# ucl.net
KiCad netlist of a schematic drawn in EAGLE
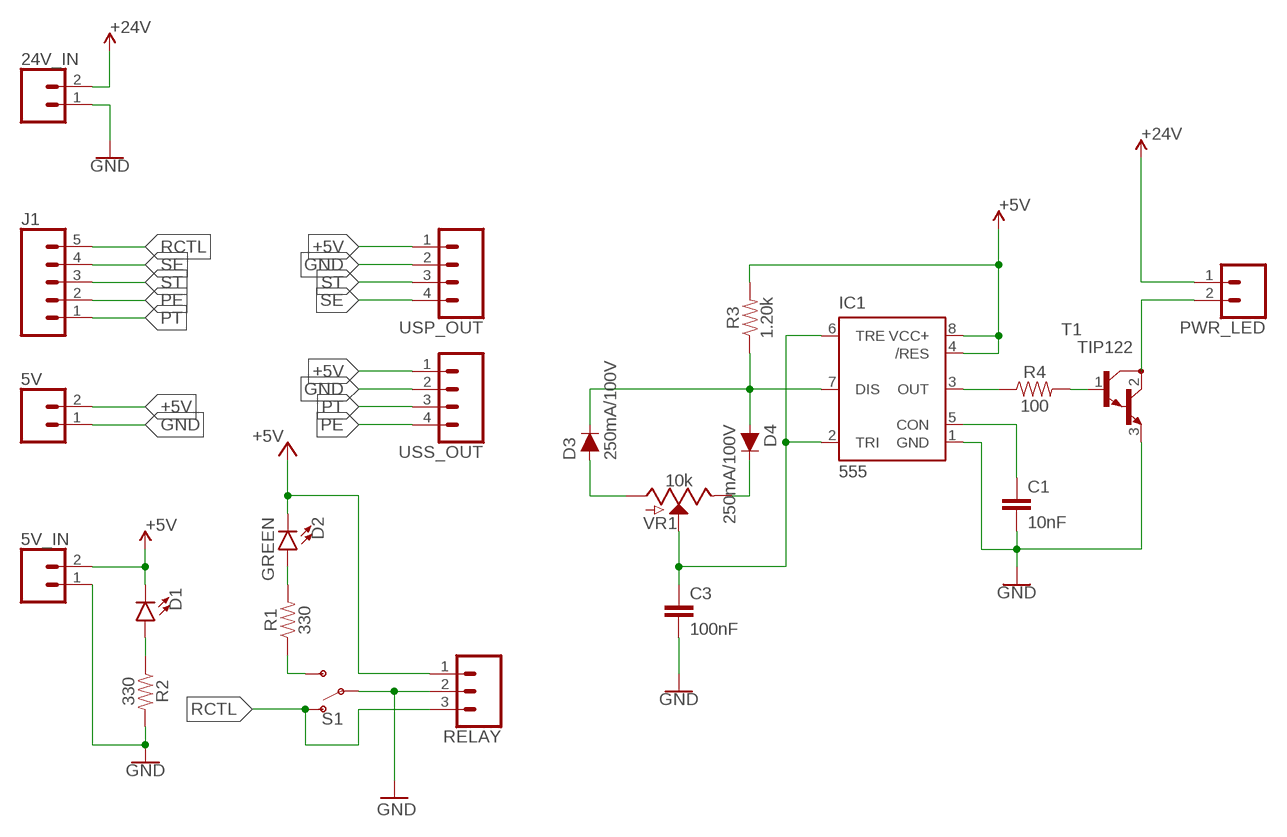
[diagram p0: schematic, sheet 1]

(export (version "E")
  (design (tool "Eeschema 10.0.6"))
  (components
    (comp (ref "5V")
      (value "CONN_02POLAR")
      (footprint "eagle-import:MOLEX-1X2")
      (libsource (lib "eagle-import") (part "CONN_02POLAR"))
    )
    (comp (ref "5V_IN")
      (value "CONN_02POLAR_LOCK")
      (footprint "eagle-import:MOLEX-1X2_LOCK")
      (libsource (lib "eagle-import") (part "CONN_02POLAR_LOCK"))
    )
    (comp (ref "24V_IN")
      (value "CONN_02POLAR_LOCK")
      (footprint "eagle-import:MOLEX-1X2_LOCK")
      (libsource (lib "eagle-import") (part "CONN_02POLAR_LOCK"))
    )
    (comp (ref "C1")
      (value "10nF")
      (footprint "eagle-import:0402-TIGHT")
      (libsource (lib "eagle-import") (part "10NF-0402T-25V-10%"))
    )
    (comp (ref "C3")
      (value "100nF")
      (footprint "eagle-import:0402-TIGHT")
      (libsource (lib "eagle-import") (part "47NF-0402_TIGHT-25V-10%-X7R"))
    )
    (comp (ref "D1")
      (value "LED1206")
      (footprint "eagle-import:LED-1206")
      (libsource (lib "eagle-import") (part "LED1206"))
    )
    (comp (ref "D2")
      (value "GREEN")
      (footprint "eagle-import:LED-1206")
      (libsource (lib "eagle-import") (part "LED-GREEN1206"))
    )
    (comp (ref "D3")
      (value "250mA/100V")
      (footprint "eagle-import:SOD-323")
      (libsource (lib "eagle-import") (part "DIODE-BAS16J"))
    )
    (comp (ref "D4")
      (value "250mA/100V")
      (footprint "eagle-import:SOD-323")
      (libsource (lib "eagle-import") (part "DIODE-BAS16J"))
    )
    (comp (ref "IC1")
      (value "555")
      (footprint "eagle-import:SO08")
      (libsource (lib "eagle-import") (part "555D"))
    )
    (comp (ref "J1")
      (value "CONN_05")
      (footprint "eagle-import:1X05")
      (libsource (lib "eagle-import") (part "CONN_05"))
    )
    (comp (ref "PWR_LED")
      (value "CONN_02POLAR_LOCK")
      (footprint "eagle-import:MOLEX-1X2_LOCK")
      (libsource (lib "eagle-import") (part "CONN_02POLAR_LOCK"))
    )
    (comp (ref "R1")
      (value "330")
      (footprint "eagle-import:0603")
      (libsource (lib "eagle-import") (part "330OHM-0603-1/10W-1%"))
    )
    (comp (ref "R2")
      (value "330")
      (footprint "eagle-import:0603")
      (libsource (lib "eagle-import") (part "330OHM-0603-1/10W-1%"))
    )
    (comp (ref "R3")
      (value "1.20k")
      (footprint "eagle-import:0603")
      (libsource (lib "eagle-import") (part "1.20KOHM-0603-1/10W-1%"))
    )
    (comp (ref "R4")
      (value "100")
      (footprint "eagle-import:0603")
      (libsource (lib "eagle-import") (part "100OHM-0603-1/4W-5%"))
    )
    (comp (ref "RELAY")
      (value "CONN_03POLAR_LOCK")
      (footprint "eagle-import:MOLEX-1X3_LOCK")
      (libsource (lib "eagle-import") (part "CONN_03POLAR_LOCK"))
    )
    (comp (ref "S1")
      (value "SWITCH-SPDT-PTH-11.6X4.0MM-KIT")
      (footprint "eagle-import:SWITCH_SPDT_PTH_11.6X4.0MM_KIT")
      (libsource (lib "eagle-import") (part "SWITCH-SPDT-PTH-11.6X4.0MM-KIT"))
    )
    (comp (ref "T1")
      (value "TIP122")
      (footprint "eagle-import:TO220")
      (libsource (lib "eagle-import") (part "TIP122"))
    )
    (comp (ref "USP_OUT")
      (value "CONN_04POLAR_LOCK")
      (footprint "eagle-import:MOLEX-1X4_LOCK")
      (libsource (lib "eagle-import") (part "CONN_04POLAR_LOCK"))
    )
    (comp (ref "USS_OUT")
      (value "CONN_04POLAR_LOCK")
      (footprint "eagle-import:MOLEX-1X4_LOCK")
      (libsource (lib "eagle-import") (part "CONN_04POLAR_LOCK"))
    )
    (comp (ref "VR1")
      (value "10k")
      (footprint "eagle-import:POT-PTH-ALPS")
      (libsource (lib "eagle-import") (part "POTENTIOMETER-PTH-9MM-1/20W-20%"))
    )
  )
  (nets
    (net (code "1") (name "+5V") (class "Default")
      (node (ref "5V") (pin "2") (pinfunction "2_2") (pintype "passive"))
      (node (ref "5V_IN") (pin "2") (pinfunction "2_2") (pintype "passive"))
      (node (ref "D1") (pin "C") (pinfunction "C_C") (pintype "passive"))
      (node (ref "D2") (pin "C") (pinfunction "C_C") (pintype "passive"))
      (node (ref "IC1") (pin "4") (pinfunction "/RES_4") (pintype "input"))
      (node (ref "IC1") (pin "8") (pinfunction "VCC+_8") (pintype "power_in"))
      (node (ref "R3") (pin "2") (pinfunction "2_2") (pintype "passive"))
      (node (ref "RELAY") (pin "1") (pinfunction "1_1") (pintype "passive"))
      (node (ref "USP_OUT") (pin "1") (pinfunction "1_1") (pintype "passive"))
      (node (ref "USS_OUT") (pin "1") (pinfunction "1_1") (pintype "passive"))
    )
    (net (code "2") (name "GND") (class "Default")
      (node (ref "24V_IN") (pin "1") (pinfunction "1_1") (pintype "passive"))
      (node (ref "5V") (pin "1") (pinfunction "1_1") (pintype "passive"))
      (node (ref "5V_IN") (pin "1") (pinfunction "1_1") (pintype "passive"))
      (node (ref "C1") (pin "2") (pinfunction "2_2") (pintype "passive"))
      (node (ref "C3") (pin "2") (pinfunction "2_2") (pintype "passive"))
      (node (ref "IC1") (pin "1") (pinfunction "GND_1") (pintype "power_in"))
      (node (ref "R2") (pin "2") (pinfunction "2_2") (pintype "passive"))
      (node (ref "RELAY") (pin "2") (pinfunction "2_2") (pintype "passive"))
      (node (ref "S1") (pin "2") (pinfunction "P_2") (pintype "passive"))
      (node (ref "T1") (pin "3") (pinfunction "E_3") (pintype "passive"))
      (node (ref "USP_OUT") (pin "2") (pinfunction "2_2") (pintype "passive"))
      (node (ref "USS_OUT") (pin "2") (pinfunction "2_2") (pintype "passive"))
    )
    (net (code "3") (name "Net-(D1-PadA)") (class "Default")
      (node (ref "D1") (pin "A") (pinfunction "A_A") (pintype "passive"))
      (node (ref "R2") (pin "1") (pinfunction "1_1") (pintype "passive"))
    )
    (net (code "4") (name "Net-(D2-PadA)") (class "Default")
      (node (ref "D2") (pin "A") (pinfunction "A_A") (pintype "passive"))
      (node (ref "R1") (pin "2") (pinfunction "2_2") (pintype "passive"))
    )
    (net (code "5") (name "Net-(IC1-CON)") (class "Default")
      (node (ref "C1") (pin "1") (pinfunction "1_1") (pintype "passive"))
      (node (ref "IC1") (pin "5") (pinfunction "CON_5") (pintype "input"))
    )
    (net (code "6") (name "Net-(IC1-DIS)") (class "Default")
      (node (ref "D3") (pin "C") (pinfunction "C_C") (pintype "passive"))
      (node (ref "D4") (pin "A") (pinfunction "A_A") (pintype "passive"))
      (node (ref "IC1") (pin "7") (pinfunction "DIS_7") (pintype "input"))
      (node (ref "R3") (pin "1") (pinfunction "1_1") (pintype "passive"))
    )
    (net (code "7") (name "Net-(IC1-OUT)") (class "Default")
      (node (ref "IC1") (pin "3") (pinfunction "OUT_3") (pintype "output"))
      (node (ref "R4") (pin "1") (pinfunction "1_1") (pintype "passive"))
    )
    (net (code "8") (name "Net-(IC1-TRE)") (class "Default")
      (node (ref "C3") (pin "1") (pinfunction "1_1") (pintype "passive"))
      (node (ref "IC1") (pin "2") (pinfunction "TRI_2") (pintype "input"))
      (node (ref "IC1") (pin "6") (pinfunction "TRE_6") (pintype "input"))
      (node (ref "VR1") (pin "P$2") (pinfunction "S_P$2") (pintype "passive"))
    )
    (net (code "9") (name "Net-(S1-S)") (class "Default")
      (node (ref "R1") (pin "1") (pinfunction "1_1") (pintype "passive"))
      (node (ref "S1") (pin "3") (pinfunction "S_3") (pintype "passive"))
    )
    (net (code "10") (name "Net-(T1-B)") (class "Default")
      (node (ref "R4") (pin "2") (pinfunction "2_2") (pintype "passive"))
      (node (ref "T1") (pin "1") (pinfunction "B_1") (pintype "passive"))
    )
    (net (code "11") (name "Net-(T1-C)") (class "Default")
      (node (ref "PWR_LED") (pin "2") (pinfunction "2_2") (pintype "passive"))
      (node (ref "T1") (pin "2") (pinfunction "C_2") (pintype "passive"))
    )
    (net (code "12") (name "Net-(VR1-A)") (class "Default")
      (node (ref "D3") (pin "A") (pinfunction "A_A") (pintype "passive"))
      (node (ref "VR1") (pin "P$3") (pinfunction "A_P$3") (pintype "passive"))
    )
    (net (code "13") (name "Net-(VR1-E)") (class "Default")
      (node (ref "D4") (pin "C") (pinfunction "C_C") (pintype "passive"))
      (node (ref "VR1") (pin "P$1") (pinfunction "E_P$1") (pintype "passive"))
    )
    (net (code "14") (name "PE") (class "Default")
      (node (ref "J1") (pin "2") (pinfunction "2_2") (pintype "passive"))
      (node (ref "USS_OUT") (pin "4") (pinfunction "4_4") (pintype "passive"))
    )
    (net (code "15") (name "PT") (class "Default")
      (node (ref "J1") (pin "1") (pinfunction "1_1") (pintype "passive"))
      (node (ref "USS_OUT") (pin "3") (pinfunction "3_3") (pintype "passive"))
    )
    (net (code "16") (name "RCTL") (class "Default")
      (node (ref "J1") (pin "5") (pinfunction "5_5") (pintype "passive"))
      (node (ref "RELAY") (pin "3") (pinfunction "3_3") (pintype "passive"))
      (node (ref "S1") (pin "1") (pinfunction "O_1") (pintype "passive"))
    )
    (net (code "17") (name "SE") (class "Default")
      (node (ref "J1") (pin "4") (pinfunction "4_4") (pintype "passive"))
      (node (ref "USP_OUT") (pin "4") (pinfunction "4_4") (pintype "passive"))
    )
    (net (code "18") (name "ST") (class "Default")
      (node (ref "J1") (pin "3") (pinfunction "3_3") (pintype "passive"))
      (node (ref "USP_OUT") (pin "3") (pinfunction "3_3") (pintype "passive"))
    )
    (net (code "19") (name "VCC_1") (class "Default")
      (node (ref "24V_IN") (pin "2") (pinfunction "2_2") (pintype "passive"))
      (node (ref "PWR_LED") (pin "1") (pinfunction "1_1") (pintype "passive"))
    )
  )
)
